# amirgb2vga.net
KiCad netlist of a schematic drawn in EAGLE
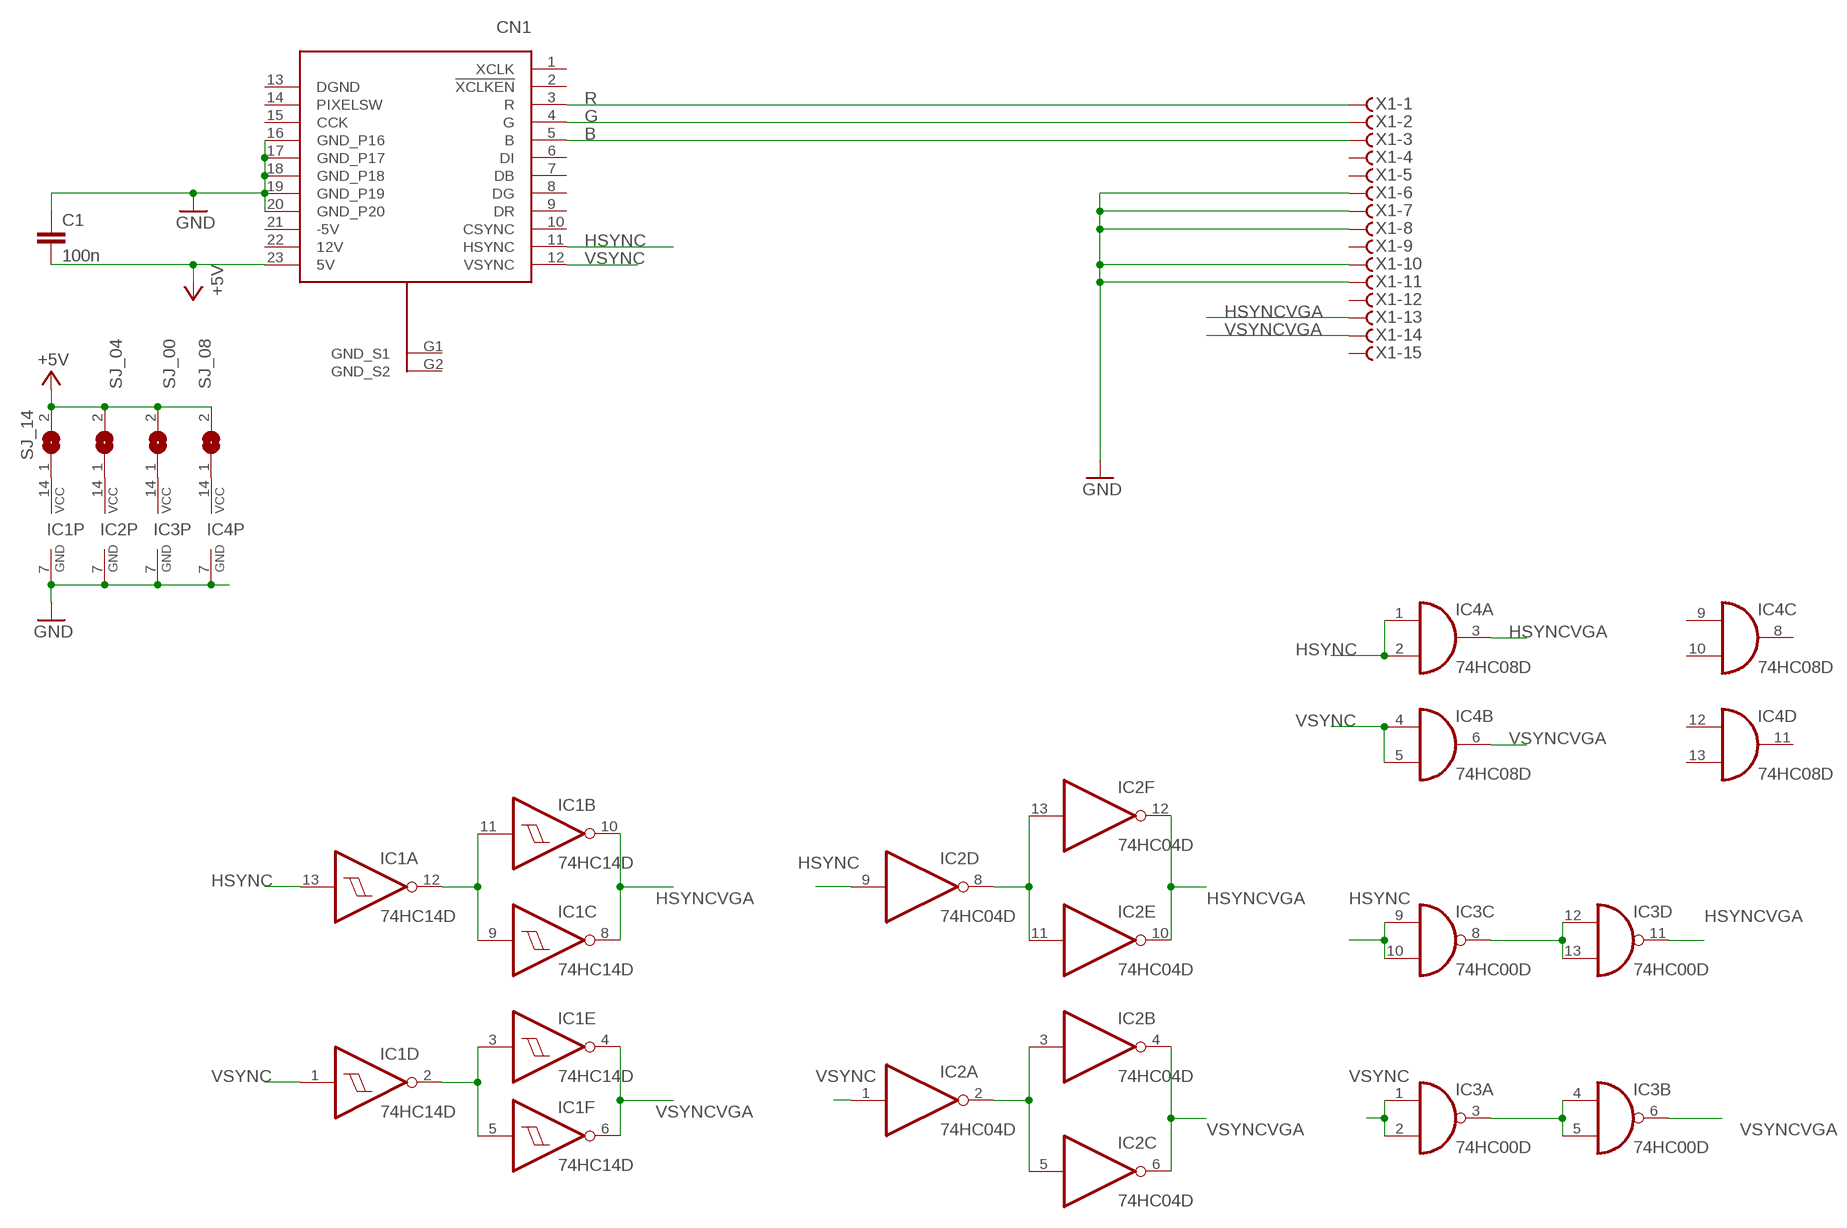
[diagram p0: schematic, sheet 1]

(export (version "E")
  (design (tool "Eeschema 10.0.6"))
  (components
    (comp (ref "C1")
      (value "100n")
      (footprint "eagle-import:C0805")
      (libsource (lib "eagle-import") (part "C-EUC0805"))
    )
    (comp (ref "CN1")
      (value "VIDEO_PORT_MALE_23D_SUB_F")
      (footprint "eagle-import:F23H_FC")
      (libsource (lib "eagle-import") (part "VIDEO_PORT_MALE_23D_SUB_F"))
    )
    (comp (ref "IC1")
      (value "74HC14D")
      (footprint "eagle-import:SO14")
      (libsource (lib "eagle-import") (part "7414DHC"))
    )
    (comp (ref "IC2")
      (value "74HC04D")
      (footprint "eagle-import:SO14")
      (libsource (lib "eagle-import") (part "7404DHC"))
    )
    (comp (ref "IC3")
      (value "74HC00D")
      (footprint "eagle-import:SO14")
      (libsource (lib "eagle-import") (part "7400DHC"))
    )
    (comp (ref "IC4")
      (value "74HC08D")
      (footprint "eagle-import:SO14")
      (libsource (lib "eagle-import") (part "7408DHC"))
    )
    (comp (ref "SJ_00")
      (value "SJ")
      (footprint "eagle-import:SJ")
      (libsource (lib "eagle-import") (part "SJ"))
    )
    (comp (ref "SJ_04")
      (value "SJ")
      (footprint "eagle-import:SJ")
      (libsource (lib "eagle-import") (part "SJ"))
    )
    (comp (ref "SJ_08")
      (value "SJ")
      (footprint "eagle-import:SJ")
      (libsource (lib "eagle-import") (part "SJ"))
    )
    (comp (ref "SJ_14")
      (value "SJ")
      (footprint "eagle-import:SJ")
      (libsource (lib "eagle-import") (part "SJ"))
    )
    (comp (ref "X1")
      (value "HF15HS")
      (footprint "eagle-import:HDF15H")
      (libsource (lib "eagle-import") (part "HF15?SH"))
    )
  )
  (nets
    (net (code "1") (name "+5V") (class "Default")
      (node (ref "C1") (pin "2") (pinfunction "2_2") (pintype "passive"))
      (node (ref "CN1") (pin "23") (pinfunction "5V_23") (pintype "bidirectional"))
      (node (ref "SJ_00") (pin "2") (pinfunction "2_2") (pintype "passive"))
      (node (ref "SJ_04") (pin "2") (pinfunction "2_2") (pintype "passive"))
      (node (ref "SJ_08") (pin "2") (pinfunction "2_2") (pintype "passive"))
      (node (ref "SJ_14") (pin "2") (pinfunction "2_2") (pintype "passive"))
    )
    (net (code "2") (name "/B") (class "Default")
      (node (ref "CN1") (pin "5") (pinfunction "B_5") (pintype "bidirectional"))
      (node (ref "X1") (pin "3") (pinfunction "F_3") (pintype "passive"))
    )
    (net (code "3") (name "/G") (class "Default")
      (node (ref "CN1") (pin "4") (pinfunction "G_4") (pintype "bidirectional"))
      (node (ref "X1") (pin "2") (pinfunction "F_2") (pintype "passive"))
    )
    (net (code "4") (name "/GND_S1") (class "Default")
      (node (ref "CN1") (pin "G1") (pinfunction "GND_S1_G1") (pintype "power_in"))
    )
    (net (code "5") (name "/GND_S2") (class "Default")
      (node (ref "CN1") (pin "G2") (pinfunction "GND_S2_G2") (pintype "power_in"))
    )
    (net (code "6") (name "/HSYNC") (class "Default")
      (node (ref "CN1") (pin "11") (pinfunction "HSYNC_11") (pintype "bidirectional"))
      (node (ref "IC1") (pin "13") (pinfunction "I_13") (pintype "input"))
      (node (ref "IC2") (pin "9") (pinfunction "I_9") (pintype "input"))
      (node (ref "IC3") (pin "10") (pinfunction "I1_10") (pintype "input"))
      (node (ref "IC3") (pin "9") (pinfunction "I0_9") (pintype "input"))
      (node (ref "IC4") (pin "1") (pinfunction "I0_1") (pintype "input"))
      (node (ref "IC4") (pin "2") (pinfunction "I1_2") (pintype "input"))
    )
    (net (code "7") (name "/HSYNCVGA") (class "Default")
      (node (ref "IC1") (pin "10") (pinfunction "O_10") (pintype "output"))
      (node (ref "IC1") (pin "8") (pinfunction "O_8") (pintype "output"))
      (node (ref "IC2") (pin "10") (pinfunction "O_10") (pintype "output"))
      (node (ref "IC2") (pin "12") (pinfunction "O_12") (pintype "output"))
      (node (ref "IC3") (pin "11") (pinfunction "O_11") (pintype "output"))
      (node (ref "IC4") (pin "3") (pinfunction "O_3") (pintype "output"))
      (node (ref "X1") (pin "13") (pinfunction "F_13") (pintype "passive"))
    )
    (net (code "8") (name "/R") (class "Default")
      (node (ref "CN1") (pin "3") (pinfunction "R_3") (pintype "bidirectional"))
      (node (ref "X1") (pin "1") (pinfunction "F_1") (pintype "passive"))
    )
    (net (code "9") (name "/VSYNC") (class "Default")
      (node (ref "CN1") (pin "12") (pinfunction "VSYNC_12") (pintype "bidirectional"))
      (node (ref "IC1") (pin "1") (pinfunction "I_1") (pintype "input"))
      (node (ref "IC2") (pin "1") (pinfunction "I_1") (pintype "input"))
      (node (ref "IC3") (pin "1") (pinfunction "I0_1") (pintype "input"))
      (node (ref "IC3") (pin "2") (pinfunction "I1_2") (pintype "input"))
      (node (ref "IC4") (pin "4") (pinfunction "I0_4") (pintype "input"))
      (node (ref "IC4") (pin "5") (pinfunction "I1_5") (pintype "input"))
    )
    (net (code "10") (name "/VSYNCVGA") (class "Default")
      (node (ref "IC1") (pin "4") (pinfunction "O_4") (pintype "output"))
      (node (ref "IC1") (pin "6") (pinfunction "O_6") (pintype "output"))
      (node (ref "IC2") (pin "4") (pinfunction "O_4") (pintype "output"))
      (node (ref "IC2") (pin "6") (pinfunction "O_6") (pintype "output"))
      (node (ref "IC3") (pin "6") (pinfunction "O_6") (pintype "output"))
      (node (ref "IC4") (pin "6") (pinfunction "O_6") (pintype "output"))
      (node (ref "X1") (pin "14") (pinfunction "F_14") (pintype "passive"))
    )
    (net (code "11") (name "GND") (class "Default")
      (node (ref "C1") (pin "1") (pinfunction "1_1") (pintype "passive"))
      (node (ref "CN1") (pin "16") (pinfunction "GND_P16_16") (pintype "bidirectional"))
      (node (ref "CN1") (pin "17") (pinfunction "GND_P17_17") (pintype "bidirectional"))
      (node (ref "CN1") (pin "18") (pinfunction "GND_P18_18") (pintype "bidirectional"))
      (node (ref "CN1") (pin "19") (pinfunction "GND_P19_19") (pintype "bidirectional"))
      (node (ref "CN1") (pin "20") (pinfunction "GND_P20_20") (pintype "bidirectional"))
      (node (ref "IC1") (pin "7") (pinfunction "GND_7") (pintype "power_in"))
      (node (ref "IC2") (pin "7") (pinfunction "GND_7") (pintype "power_in"))
      (node (ref "IC3") (pin "7") (pinfunction "GND_7") (pintype "power_in"))
      (node (ref "IC4") (pin "7") (pinfunction "GND_7") (pintype "power_in"))
      (node (ref "X1") (pin "10") (pinfunction "F_10") (pintype "passive"))
      (node (ref "X1") (pin "11") (pinfunction "F_11") (pintype "passive"))
      (node (ref "X1") (pin "6") (pinfunction "F_6") (pintype "passive"))
      (node (ref "X1") (pin "7") (pinfunction "F_7") (pintype "passive"))
      (node (ref "X1") (pin "8") (pinfunction "F_8") (pintype "passive"))
    )
    (net (code "12") (name "Net-(IC1A-O)") (class "Default")
      (node (ref "IC1") (pin "11") (pinfunction "I_11") (pintype "input"))
      (node (ref "IC1") (pin "12") (pinfunction "O_12") (pintype "output"))
      (node (ref "IC1") (pin "9") (pinfunction "I_9") (pintype "input"))
    )
    (net (code "13") (name "Net-(IC1D-O)") (class "Default")
      (node (ref "IC1") (pin "2") (pinfunction "O_2") (pintype "output"))
      (node (ref "IC1") (pin "3") (pinfunction "I_3") (pintype "input"))
      (node (ref "IC1") (pin "5") (pinfunction "I_5") (pintype "input"))
    )
    (net (code "14") (name "Net-(IC1G-VCC)") (class "Default")
      (node (ref "IC1") (pin "14") (pinfunction "VCC_14") (pintype "power_in"))
      (node (ref "SJ_14") (pin "1") (pinfunction "1_1") (pintype "passive"))
    )
    (net (code "15") (name "Net-(IC2A-O)") (class "Default")
      (node (ref "IC2") (pin "2") (pinfunction "O_2") (pintype "output"))
      (node (ref "IC2") (pin "3") (pinfunction "I_3") (pintype "input"))
      (node (ref "IC2") (pin "5") (pinfunction "I_5") (pintype "input"))
    )
    (net (code "16") (name "Net-(IC2D-O)") (class "Default")
      (node (ref "IC2") (pin "11") (pinfunction "I_11") (pintype "input"))
      (node (ref "IC2") (pin "13") (pinfunction "I_13") (pintype "input"))
      (node (ref "IC2") (pin "8") (pinfunction "O_8") (pintype "output"))
    )
    (net (code "17") (name "Net-(IC2G-VCC)") (class "Default")
      (node (ref "IC2") (pin "14") (pinfunction "VCC_14") (pintype "power_in"))
      (node (ref "SJ_04") (pin "1") (pinfunction "1_1") (pintype "passive"))
    )
    (net (code "18") (name "Net-(IC3A-O)") (class "Default")
      (node (ref "IC3") (pin "3") (pinfunction "O_3") (pintype "output"))
      (node (ref "IC3") (pin "4") (pinfunction "I0_4") (pintype "input"))
      (node (ref "IC3") (pin "5") (pinfunction "I1_5") (pintype "input"))
    )
    (net (code "19") (name "Net-(IC3C-O)") (class "Default")
      (node (ref "IC3") (pin "12") (pinfunction "I0_12") (pintype "input"))
      (node (ref "IC3") (pin "13") (pinfunction "I1_13") (pintype "input"))
      (node (ref "IC3") (pin "8") (pinfunction "O_8") (pintype "output"))
    )
    (net (code "20") (name "Net-(IC3E-VCC)") (class "Default")
      (node (ref "IC3") (pin "14") (pinfunction "VCC_14") (pintype "power_in"))
      (node (ref "SJ_00") (pin "1") (pinfunction "1_1") (pintype "passive"))
    )
    (net (code "21") (name "Net-(IC4E-VCC)") (class "Default")
      (node (ref "IC4") (pin "14") (pinfunction "VCC_14") (pintype "power_in"))
      (node (ref "SJ_08") (pin "1") (pinfunction "1_1") (pintype "passive"))
    )
    (net (code "22") (name "unconnected-(CN1--5V-Pad21)") (class "Default")
      (node (ref "CN1") (pin "21") (pinfunction "-5V_21") (pintype "bidirectional"))
    )
    (net (code "23") (name "unconnected-(CN1-12V-Pad22)") (class "Default")
      (node (ref "CN1") (pin "22") (pinfunction "12V_22") (pintype "bidirectional"))
    )
    (net (code "24") (name "unconnected-(CN1-CCK-Pad15)") (class "Default")
      (node (ref "CN1") (pin "15") (pinfunction "CCK_15") (pintype "bidirectional"))
    )
    (net (code "25") (name "unconnected-(CN1-CSYNC-Pad10)") (class "Default")
      (node (ref "CN1") (pin "10") (pinfunction "CSYNC_10") (pintype "bidirectional"))
    )
    (net (code "26") (name "unconnected-(CN1-DB-Pad7)") (class "Default")
      (node (ref "CN1") (pin "7") (pinfunction "DB_7") (pintype "bidirectional"))
    )
    (net (code "27") (name "unconnected-(CN1-DG-Pad8)") (class "Default")
      (node (ref "CN1") (pin "8") (pinfunction "DG_8") (pintype "bidirectional"))
    )
    (net (code "28") (name "unconnected-(CN1-DGND-Pad13)") (class "Default")
      (node (ref "CN1") (pin "13") (pinfunction "DGND_13") (pintype "bidirectional"))
    )
    (net (code "29") (name "unconnected-(CN1-DI-Pad6)") (class "Default")
      (node (ref "CN1") (pin "6") (pinfunction "DI_6") (pintype "bidirectional"))
    )
    (net (code "30") (name "unconnected-(CN1-DR-Pad9)") (class "Default")
      (node (ref "CN1") (pin "9") (pinfunction "DR_9") (pintype "bidirectional"))
    )
    (net (code "31") (name "unconnected-(CN1-PIXELSW-Pad14)") (class "Default")
      (node (ref "CN1") (pin "14") (pinfunction "PIXELSW_14") (pintype "bidirectional"))
    )
    (net (code "32") (name "unconnected-(CN1-XCLK-Pad1)") (class "Default")
      (node (ref "CN1") (pin "1") (pinfunction "XCLK_1") (pintype "bidirectional"))
    )
    (net (code "33") (name "unconnected-(CN1-~{XCLKEN}-Pad2)") (class "Default")
      (node (ref "CN1") (pin "2") (pinfunction "~{XCLKEN}_2") (pintype "bidirectional"))
    )
    (net (code "34") (name "unconnected-(IC4C-I0-Pad9)") (class "Default")
      (node (ref "IC4") (pin "9") (pinfunction "I0_9") (pintype "input"))
    )
    (net (code "35") (name "unconnected-(IC4C-I1-Pad10)") (class "Default")
      (node (ref "IC4") (pin "10") (pinfunction "I1_10") (pintype "input"))
    )
    (net (code "36") (name "unconnected-(IC4C-O-Pad8)") (class "Default")
      (node (ref "IC4") (pin "8") (pinfunction "O_8") (pintype "output"))
    )
    (net (code "37") (name "unconnected-(IC4D-I0-Pad12)") (class "Default")
      (node (ref "IC4") (pin "12") (pinfunction "I0_12") (pintype "input"))
    )
    (net (code "38") (name "unconnected-(IC4D-I1-Pad13)") (class "Default")
      (node (ref "IC4") (pin "13") (pinfunction "I1_13") (pintype "input"))
    )
    (net (code "39") (name "unconnected-(IC4D-O-Pad11)") (class "Default")
      (node (ref "IC4") (pin "11") (pinfunction "O_11") (pintype "output"))
    )
    (net (code "40") (name "unconnected-(X1D-F-Pad12)") (class "Default")
      (node (ref "X1") (pin "12") (pinfunction "F_12") (pintype "passive"))
    )
    (net (code "41") (name "unconnected-(X1G-F-Pad15)") (class "Default")
      (node (ref "X1") (pin "15") (pinfunction "F_15") (pintype "passive"))
    )
    (net (code "42") (name "unconnected-(X1J-F-Pad4)") (class "Default")
      (node (ref "X1") (pin "4") (pinfunction "F_4") (pintype "passive"))
    )
    (net (code "43") (name "unconnected-(X1K-F-Pad5)") (class "Default")
      (node (ref "X1") (pin "5") (pinfunction "F_5") (pintype "passive"))
    )
    (net (code "44") (name "unconnected-(X1O-F-Pad9)") (class "Default")
      (node (ref "X1") (pin "9") (pinfunction "F_9") (pintype "passive"))
    )
  )
)
